# Reed_Switch.net
KiCad netlist of a schematic drawn in Altium Designer
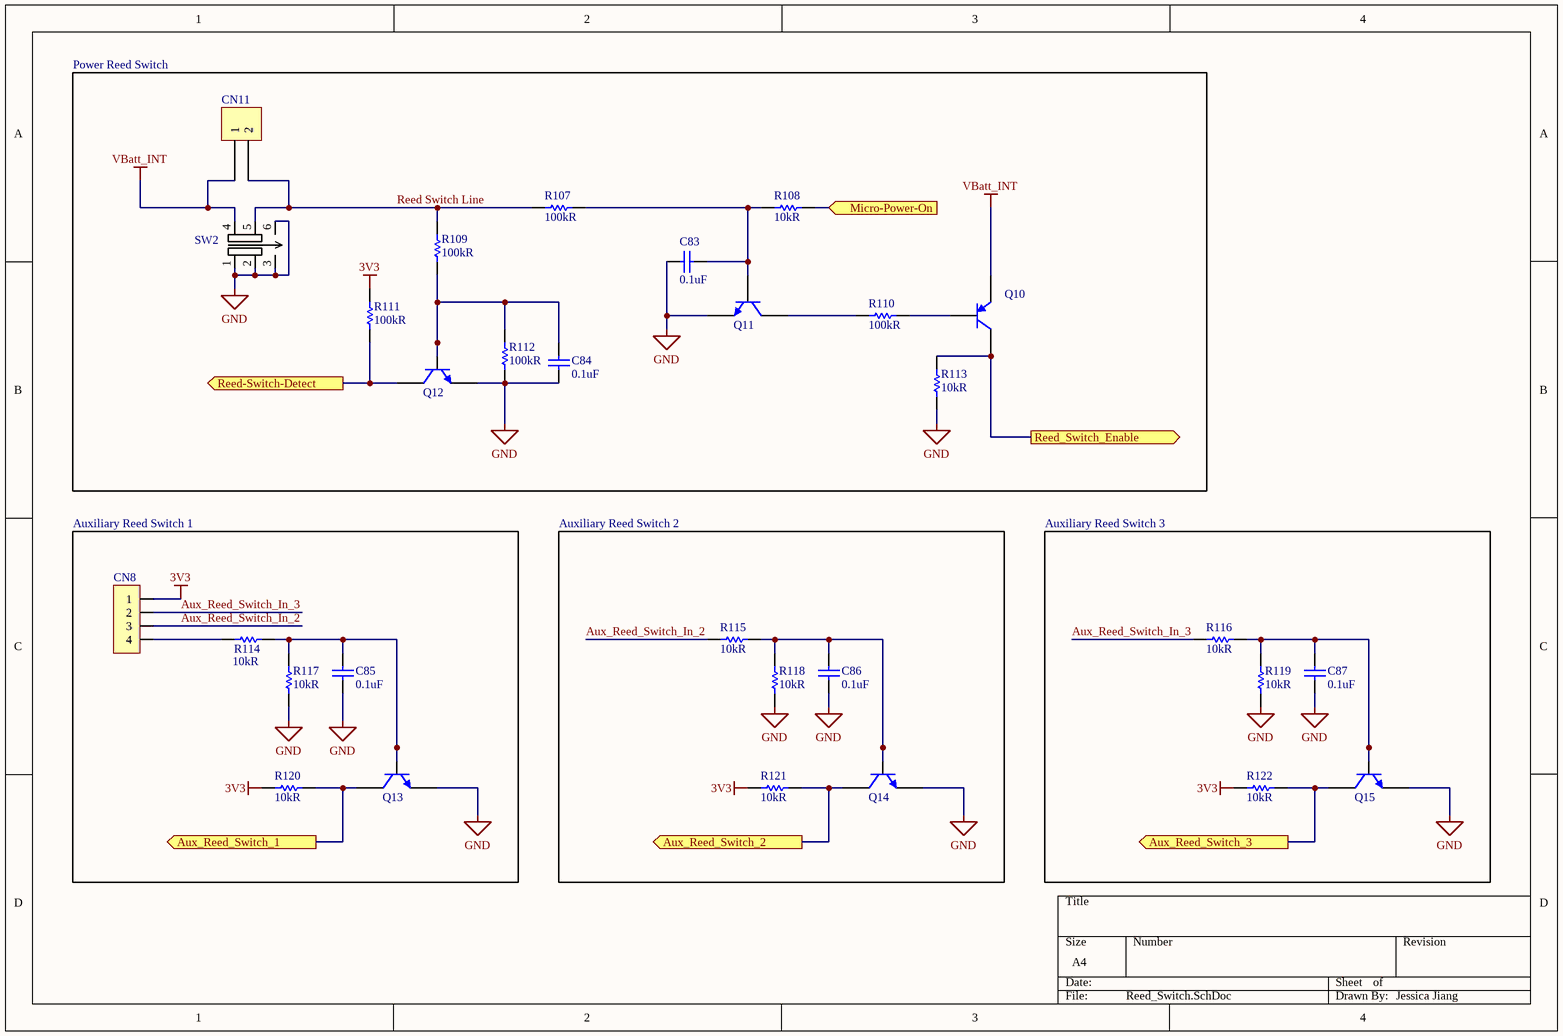
[diagram p0: Reed_Switch.SchDoc]

(export (version "E")
  (design (tool "Eeschema 10.0.6"))
  (components
    (comp (ref "C83")
      (value "CL10B104JB8NNNC")
      (footprint "FP-CL10-0_1-IPC_A")
      (description "CAP CER 0.1UF 50V X7R 0603")
      (fields
        (field (name "TOLERANCE") "5%")
        (field (name "VOLTAGE") "50V")
        (field (name "CAPACITANCE") "0.1uF")
      )
      (libsource (lib "AUVIC") (part "CAP-NP-2"))
    )
    (comp (ref "C84")
      (value "CL10B104JB8NNNC")
      (footprint "FP-CL10-0_1-IPC_A")
      (description "CAP CER 0.1UF 50V X7R 0603")
      (fields
        (field (name "TOLERANCE") "5%")
        (field (name "VOLTAGE") "50V")
        (field (name "CAPACITANCE") "0.1uF")
      )
      (libsource (lib "AUVIC") (part "CAP-NP-2"))
    )
    (comp (ref "C85")
      (value "CL10B104JB8NNNC")
      (footprint "FP-CL10-0_1-IPC_A")
      (description "CAP CER 0.1UF 50V X7R 0603")
      (fields
        (field (name "TOLERANCE") "5%")
        (field (name "VOLTAGE") "50V")
        (field (name "CAPACITANCE") "0.1uF")
      )
      (libsource (lib "AUVIC") (part "CAP-NP-2"))
    )
    (comp (ref "C86")
      (value "CL10B104JB8NNNC")
      (footprint "FP-CL10-0_1-IPC_A")
      (description "CAP CER 0.1UF 50V X7R 0603")
      (fields
        (field (name "TOLERANCE") "5%")
        (field (name "VOLTAGE") "50V")
        (field (name "CAPACITANCE") "0.1uF")
      )
      (libsource (lib "AUVIC") (part "CAP-NP-2"))
    )
    (comp (ref "C87")
      (value "CL10B104JB8NNNC")
      (footprint "FP-CL10-0_1-IPC_A")
      (description "CAP CER 0.1UF 50V X7R 0603")
      (fields
        (field (name "TOLERANCE") "5%")
        (field (name "VOLTAGE") "50V")
        (field (name "CAPACITANCE") "0.1uF")
      )
      (libsource (lib "AUVIC") (part "CAP-NP-2"))
    )
    (comp (ref "CN8")
      (value "Header, Male, 1x4, RA, Pitch 0.1\" (2.54mm)")
      (footprint "HEADER, MALE, SHROUDED, 4x1, PITCH 0.1\" (2.54mm), RA")
      (description "Connector Header Through Hole, Right Angle 4 position 0.100\" (2.54mm)")
      (fields (field (name "CREATED BY") "Miguel Manguerra"))
      (libsource (lib "") (part "Symbol_1"))
    )
    (comp (ref "CN11")
      (value "1x2 Shrouded Right Angle")
      (footprint "2X1 Female Header")
      (description "02 MTE HDR SRRA LATCH")
      (libsource (lib "AUVIC") (part "1x2 Shrouded Right Angle"))
    )
    (comp (ref "Q10")
      (value "BC856A,215")
      (footprint "SOT-23")
      (description "PNP 65V 100mA 250mW")
      (libsource (lib "AUVIC") (part "BC856A,215"))
    )
    (comp (ref "Q11")
      (value "BC846B,215")
      (footprint "SOT-23")
      (description "NPN 65V 100mA 250mW")
      (fields (field (name "PUBLISHER") "Andy Bates"))
      (libsource (lib "AUVIC") (part "Symbol"))
    )
    (comp (ref "Q12")
      (value "BC846B,215")
      (footprint "SOT-23")
      (description "NPN 65V 100mA 250mW")
      (fields (field (name "PUBLISHER") "Andy Bates"))
      (libsource (lib "AUVIC") (part "Symbol"))
    )
    (comp (ref "Q13")
      (value "BC846B,215")
      (footprint "SOT-23")
      (description "NPN 65V 100mA 250mW")
      (fields (field (name "PUBLISHER") "Andy Bates"))
      (libsource (lib "AUVIC") (part "Symbol"))
    )
    (comp (ref "Q14")
      (value "BC846B,215")
      (footprint "SOT-23")
      (description "NPN 65V 100mA 250mW")
      (fields (field (name "PUBLISHER") "Andy Bates"))
      (libsource (lib "AUVIC") (part "Symbol"))
    )
    (comp (ref "Q15")
      (value "BC846B,215")
      (footprint "SOT-23")
      (description "NPN 65V 100mA 250mW")
      (fields (field (name "PUBLISHER") "Andy Bates"))
      (libsource (lib "AUVIC") (part "Symbol"))
    )
    (comp (ref "R107")
      (value "CRCW0603-100KFKEA")
      (footprint "RESC1609X50X30ML10T20")
      (description "Resistor; Thick Film; 100 Kilohms; 0.1 W; 1%; SMT; 0603; TCR 37 ppm/DegC; Tape and Reel")
      (fields (field (name "RESISTANCE") "100kR") (field (name "TOLERANCE") "1%"))
      (libsource (lib "AUVIC") (part "RES"))
    )
    (comp (ref "R108")
      (value "RC0603FR-0710KL")
      (footprint "RESC1608X55X25ML10T15")
      (description "Res General Purpose Thick Film 0603 10K Ohm 1% 1/10W ±100ppm/°C Molded SMD Paper T/R")
      (fields (field (name "RESISTANCE") "10kR") (field (name "TOLERANCE") "1%"))
      (libsource (lib "AUVIC") (part "RES-2"))
    )
    (comp (ref "R109")
      (value "CRCW0603-100KFKEA")
      (footprint "RESC1609X50X30ML10T20")
      (description "Resistor; Thick Film; 100 Kilohms; 0.1 W; 1%; SMT; 0603; TCR 37 ppm/DegC; Tape and Reel")
      (fields (field (name "RESISTANCE") "100kR") (field (name "TOLERANCE") "1%"))
      (libsource (lib "AUVIC") (part "RES"))
    )
    (comp (ref "R110")
      (value "CRCW0603-100KFKEA")
      (footprint "RESC1609X50X30ML10T20")
      (description "Resistor; Thick Film; 100 Kilohms; 0.1 W; 1%; SMT; 0603; TCR 37 ppm/DegC; Tape and Reel")
      (fields (field (name "RESISTANCE") "100kR") (field (name "TOLERANCE") "1%"))
      (libsource (lib "AUVIC") (part "RES"))
    )
    (comp (ref "R111")
      (value "CRCW0603-100KFKEA")
      (footprint "RESC1609X50X30ML10T20")
      (description "Resistor; Thick Film; 100 Kilohms; 0.1 W; 1%; SMT; 0603; TCR 37 ppm/DegC; Tape and Reel")
      (fields (field (name "RESISTANCE") "100kR") (field (name "TOLERANCE") "1%"))
      (libsource (lib "AUVIC") (part "RES"))
    )
    (comp (ref "R112")
      (value "CRCW0603-100KFKEA")
      (footprint "RESC1609X50X30ML10T20")
      (description "Resistor; Thick Film; 100 Kilohms; 0.1 W; 1%; SMT; 0603; TCR 37 ppm/DegC; Tape and Reel")
      (fields (field (name "RESISTANCE") "100kR") (field (name "TOLERANCE") "1%"))
      (libsource (lib "AUVIC") (part "RES"))
    )
    (comp (ref "R113")
      (value "RC0603FR-0710KL")
      (footprint "RESC1608X55X25ML10T15")
      (description "Res General Purpose Thick Film 0603 10K Ohm 1% 1/10W ±100ppm/°C Molded SMD Paper T/R")
      (fields (field (name "RESISTANCE") "10kR") (field (name "TOLERANCE") "1%"))
      (libsource (lib "AUVIC") (part "RES-2"))
    )
    (comp (ref "R114")
      (value "RC0603FR-0710KL")
      (footprint "RESC1608X55X25ML10T15")
      (description "Res General Purpose Thick Film 0603 10K Ohm 1% 1/10W ±100ppm/°C Molded SMD Paper T/R")
      (fields (field (name "RESISTANCE") "10kR") (field (name "TOLERANCE") "1%"))
      (libsource (lib "AUVIC") (part "RES-2"))
    )
    (comp (ref "R115")
      (value "RC0603FR-0710KL")
      (footprint "RESC1608X55X25ML10T15")
      (description "Res General Purpose Thick Film 0603 10K Ohm 1% 1/10W ±100ppm/°C Molded SMD Paper T/R")
      (fields (field (name "RESISTANCE") "10kR") (field (name "TOLERANCE") "1%"))
      (libsource (lib "AUVIC") (part "RES-2"))
    )
    (comp (ref "R116")
      (value "RC0603FR-0710KL")
      (footprint "RESC1608X55X25ML10T15")
      (description "Res General Purpose Thick Film 0603 10K Ohm 1% 1/10W ±100ppm/°C Molded SMD Paper T/R")
      (fields (field (name "RESISTANCE") "10kR") (field (name "TOLERANCE") "1%"))
      (libsource (lib "AUVIC") (part "RES-2"))
    )
    (comp (ref "R117")
      (value "RC0603FR-0710KL")
      (footprint "RESC1608X55X25ML10T15")
      (description "Res General Purpose Thick Film 0603 10K Ohm 1% 1/10W ±100ppm/°C Molded SMD Paper T/R")
      (fields (field (name "RESISTANCE") "10kR") (field (name "TOLERANCE") "1%"))
      (libsource (lib "AUVIC") (part "RES-2"))
    )
    (comp (ref "R118")
      (value "RC0603FR-0710KL")
      (footprint "RESC1608X55X25ML10T15")
      (description "Res General Purpose Thick Film 0603 10K Ohm 1% 1/10W ±100ppm/°C Molded SMD Paper T/R")
      (fields (field (name "RESISTANCE") "10kR") (field (name "TOLERANCE") "1%"))
      (libsource (lib "AUVIC") (part "RES-2"))
    )
    (comp (ref "R119")
      (value "RC0603FR-0710KL")
      (footprint "RESC1608X55X25ML10T15")
      (description "Res General Purpose Thick Film 0603 10K Ohm 1% 1/10W ±100ppm/°C Molded SMD Paper T/R")
      (fields (field (name "RESISTANCE") "10kR") (field (name "TOLERANCE") "1%"))
      (libsource (lib "AUVIC") (part "RES-2"))
    )
    (comp (ref "R120")
      (value "RC0603FR-0710KL")
      (footprint "RESC1608X55X25ML10T15")
      (description "Res General Purpose Thick Film 0603 10K Ohm 1% 1/10W ±100ppm/°C Molded SMD Paper T/R")
      (fields (field (name "RESISTANCE") "10kR") (field (name "TOLERANCE") "1%"))
      (libsource (lib "AUVIC") (part "RES-2"))
    )
    (comp (ref "R121")
      (value "RC0603FR-0710KL")
      (footprint "RESC1608X55X25ML10T15")
      (description "Res General Purpose Thick Film 0603 10K Ohm 1% 1/10W ±100ppm/°C Molded SMD Paper T/R")
      (fields (field (name "RESISTANCE") "10kR") (field (name "TOLERANCE") "1%"))
      (libsource (lib "AUVIC") (part "RES-2"))
    )
    (comp (ref "R122")
      (value "RC0603FR-0710KL")
      (footprint "RESC1608X55X25ML10T15")
      (description "Res General Purpose Thick Film 0603 10K Ohm 1% 1/10W ±100ppm/°C Molded SMD Paper T/R")
      (fields (field (name "RESISTANCE") "10kR") (field (name "TOLERANCE") "1%"))
      (libsource (lib "AUVIC") (part "RES-2"))
    )
    (comp (ref "SW2")
      (value "DPDT, 12V, 200mA, SMT")
      (footprint "CL-2B-22A")
      (fields (field (name "CREATED BY") "Lyden Smith"))
      (libsource (lib "AUVIC") (part "DPDT, 12V, 200mA, SMT"))
    )
  )
  (nets
    (net (code "1") (name "/Aux_Reed_Switch_1") (class "Default")
      (node (ref "Q13") (pin "3") (pinfunction "C_3") (pintype "passive"))
      (node (ref "R120") (pin "1") (pinfunction "1_1") (pintype "passive"))
    )
    (net (code "2") (name "/Aux_Reed_Switch_2") (class "Default")
      (node (ref "Q14") (pin "3") (pinfunction "C_3") (pintype "passive"))
      (node (ref "R121") (pin "1") (pinfunction "1_1") (pintype "passive"))
    )
    (net (code "3") (name "/Aux_Reed_Switch_3") (class "Default")
      (node (ref "Q15") (pin "3") (pinfunction "C_3") (pintype "passive"))
      (node (ref "R122") (pin "2") (pinfunction "2_2") (pintype "passive"))
    )
    (net (code "4") (name "/Aux_Reed_Switch_In_2") (class "Default")
      (node (ref "CN8") (pin "3") (pinfunction "3_3") (pintype "passive"))
      (node (ref "R115") (pin "2") (pinfunction "2_2") (pintype "passive"))
    )
    (net (code "5") (name "/Aux_Reed_Switch_In_3") (class "Default")
      (node (ref "CN8") (pin "2") (pinfunction "2_2") (pintype "passive"))
      (node (ref "R116") (pin "2") (pinfunction "2_2") (pintype "passive"))
    )
    (net (code "6") (name "/Micro-Power-On") (class "Default")
      (node (ref "R108") (pin "2") (pinfunction "2_2") (pintype "passive"))
    )
    (net (code "7") (name "/Reed Switch Line") (class "Default")
      (node (ref "CN11") (pin "2") (pinfunction "2_2") (pintype "passive"))
      (node (ref "R107") (pin "2") (pinfunction "2_2") (pintype "passive"))
      (node (ref "R109") (pin "2") (pinfunction "2_2") (pintype "passive"))
      (node (ref "SW2") (pin "5") (pinfunction "5_5") (pintype "passive"))
    )
    (net (code "8") (name "/Reed-Switch-Detect") (class "Default")
      (node (ref "Q12") (pin "3") (pinfunction "C_3") (pintype "passive"))
      (node (ref "R111") (pin "1") (pinfunction "1_1") (pintype "passive"))
    )
    (net (code "9") (name "/Reed_Switch_Enable") (class "Default")
      (node (ref "Q10") (pin "3") (pinfunction "C_3") (pintype "passive"))
      (node (ref "R113") (pin "1") (pinfunction "1_1") (pintype "passive"))
    )
    (net (code "10") (name "3V3") (class "Default")
      (node (ref "CN8") (pin "1") (pinfunction "1_1") (pintype "passive"))
      (node (ref "R111") (pin "2") (pinfunction "2_2") (pintype "passive"))
      (node (ref "R120") (pin "2") (pinfunction "2_2") (pintype "passive"))
      (node (ref "R121") (pin "2") (pinfunction "2_2") (pintype "passive"))
      (node (ref "R122") (pin "1") (pinfunction "1_1") (pintype "passive"))
    )
    (net (code "11") (name "GND") (class "Default")
      (node (ref "C83") (pin "2") (pinfunction "2_2") (pintype "passive"))
      (node (ref "C84") (pin "2") (pinfunction "2_2") (pintype "passive"))
      (node (ref "C85") (pin "2") (pinfunction "2_2") (pintype "passive"))
      (node (ref "C86") (pin "2") (pinfunction "2_2") (pintype "passive"))
      (node (ref "C87") (pin "2") (pinfunction "2_2") (pintype "passive"))
      (node (ref "Q11") (pin "2") (pinfunction "E_2") (pintype "passive"))
      (node (ref "Q12") (pin "2") (pinfunction "E_2") (pintype "passive"))
      (node (ref "Q13") (pin "2") (pinfunction "E_2") (pintype "passive"))
      (node (ref "Q14") (pin "2") (pinfunction "E_2") (pintype "passive"))
      (node (ref "Q15") (pin "2") (pinfunction "E_2") (pintype "passive"))
      (node (ref "R112") (pin "1") (pinfunction "1_1") (pintype "passive"))
      (node (ref "R113") (pin "2") (pinfunction "2_2") (pintype "passive"))
      (node (ref "R117") (pin "1") (pinfunction "1_1") (pintype "passive"))
      (node (ref "R118") (pin "1") (pinfunction "1_1") (pintype "passive"))
      (node (ref "R119") (pin "2") (pinfunction "2_2") (pintype "passive"))
      (node (ref "SW2") (pin "1") (pinfunction "1_1") (pintype "passive"))
      (node (ref "SW2") (pin "2") (pinfunction "2_2") (pintype "passive"))
      (node (ref "SW2") (pin "3") (pinfunction "3_3") (pintype "passive"))
      (node (ref "SW2") (pin "6") (pinfunction "6_6") (pintype "passive"))
    )
    (net (code "12") (name "Net-(CN8-Pad4)") (class "Default")
      (node (ref "CN8") (pin "4") (pinfunction "4_4") (pintype "passive"))
      (node (ref "R114") (pin "2") (pinfunction "2_2") (pintype "passive"))
    )
    (net (code "13") (name "Net-(Q10-B)") (class "Default")
      (node (ref "Q10") (pin "1") (pinfunction "B_1") (pintype "passive"))
      (node (ref "R110") (pin "2") (pinfunction "2_2") (pintype "passive"))
    )
    (net (code "14") (name "Net-(Q11-B)") (class "Default")
      (node (ref "C83") (pin "1") (pinfunction "1_1") (pintype "passive"))
      (node (ref "Q11") (pin "1") (pinfunction "B_1") (pintype "passive"))
      (node (ref "R107") (pin "1") (pinfunction "1_1") (pintype "passive"))
      (node (ref "R108") (pin "1") (pinfunction "1_1") (pintype "passive"))
    )
    (net (code "15") (name "Net-(Q11-C)") (class "Default")
      (node (ref "Q11") (pin "3") (pinfunction "C_3") (pintype "passive"))
      (node (ref "R110") (pin "1") (pinfunction "1_1") (pintype "passive"))
    )
    (net (code "16") (name "Net-(Q12-B)") (class "Default")
      (node (ref "C84") (pin "1") (pinfunction "1_1") (pintype "passive"))
      (node (ref "Q12") (pin "1") (pinfunction "B_1") (pintype "passive"))
      (node (ref "R109") (pin "1") (pinfunction "1_1") (pintype "passive"))
      (node (ref "R112") (pin "2") (pinfunction "2_2") (pintype "passive"))
    )
    (net (code "17") (name "Net-(Q13-B)") (class "Default")
      (node (ref "C85") (pin "1") (pinfunction "1_1") (pintype "passive"))
      (node (ref "Q13") (pin "1") (pinfunction "B_1") (pintype "passive"))
      (node (ref "R114") (pin "1") (pinfunction "1_1") (pintype "passive"))
      (node (ref "R117") (pin "2") (pinfunction "2_2") (pintype "passive"))
    )
    (net (code "18") (name "Net-(Q14-B)") (class "Default")
      (node (ref "C86") (pin "1") (pinfunction "1_1") (pintype "passive"))
      (node (ref "Q14") (pin "1") (pinfunction "B_1") (pintype "passive"))
      (node (ref "R115") (pin "1") (pinfunction "1_1") (pintype "passive"))
      (node (ref "R118") (pin "2") (pinfunction "2_2") (pintype "passive"))
    )
    (net (code "19") (name "Net-(Q15-B)") (class "Default")
      (node (ref "C87") (pin "1") (pinfunction "1_1") (pintype "passive"))
      (node (ref "Q15") (pin "1") (pinfunction "B_1") (pintype "passive"))
      (node (ref "R116") (pin "1") (pinfunction "1_1") (pintype "passive"))
      (node (ref "R119") (pin "1") (pinfunction "1_1") (pintype "passive"))
    )
    (net (code "20") (name "VBatt_INT") (class "Default")
      (node (ref "CN11") (pin "1") (pinfunction "1_1") (pintype "passive"))
      (node (ref "Q10") (pin "2") (pinfunction "E_2") (pintype "passive"))
      (node (ref "SW2") (pin "4") (pinfunction "4_4") (pintype "passive"))
    )
  )
)
